# Payload.net
KiCad netlist of a schematic drawn in EAGLE
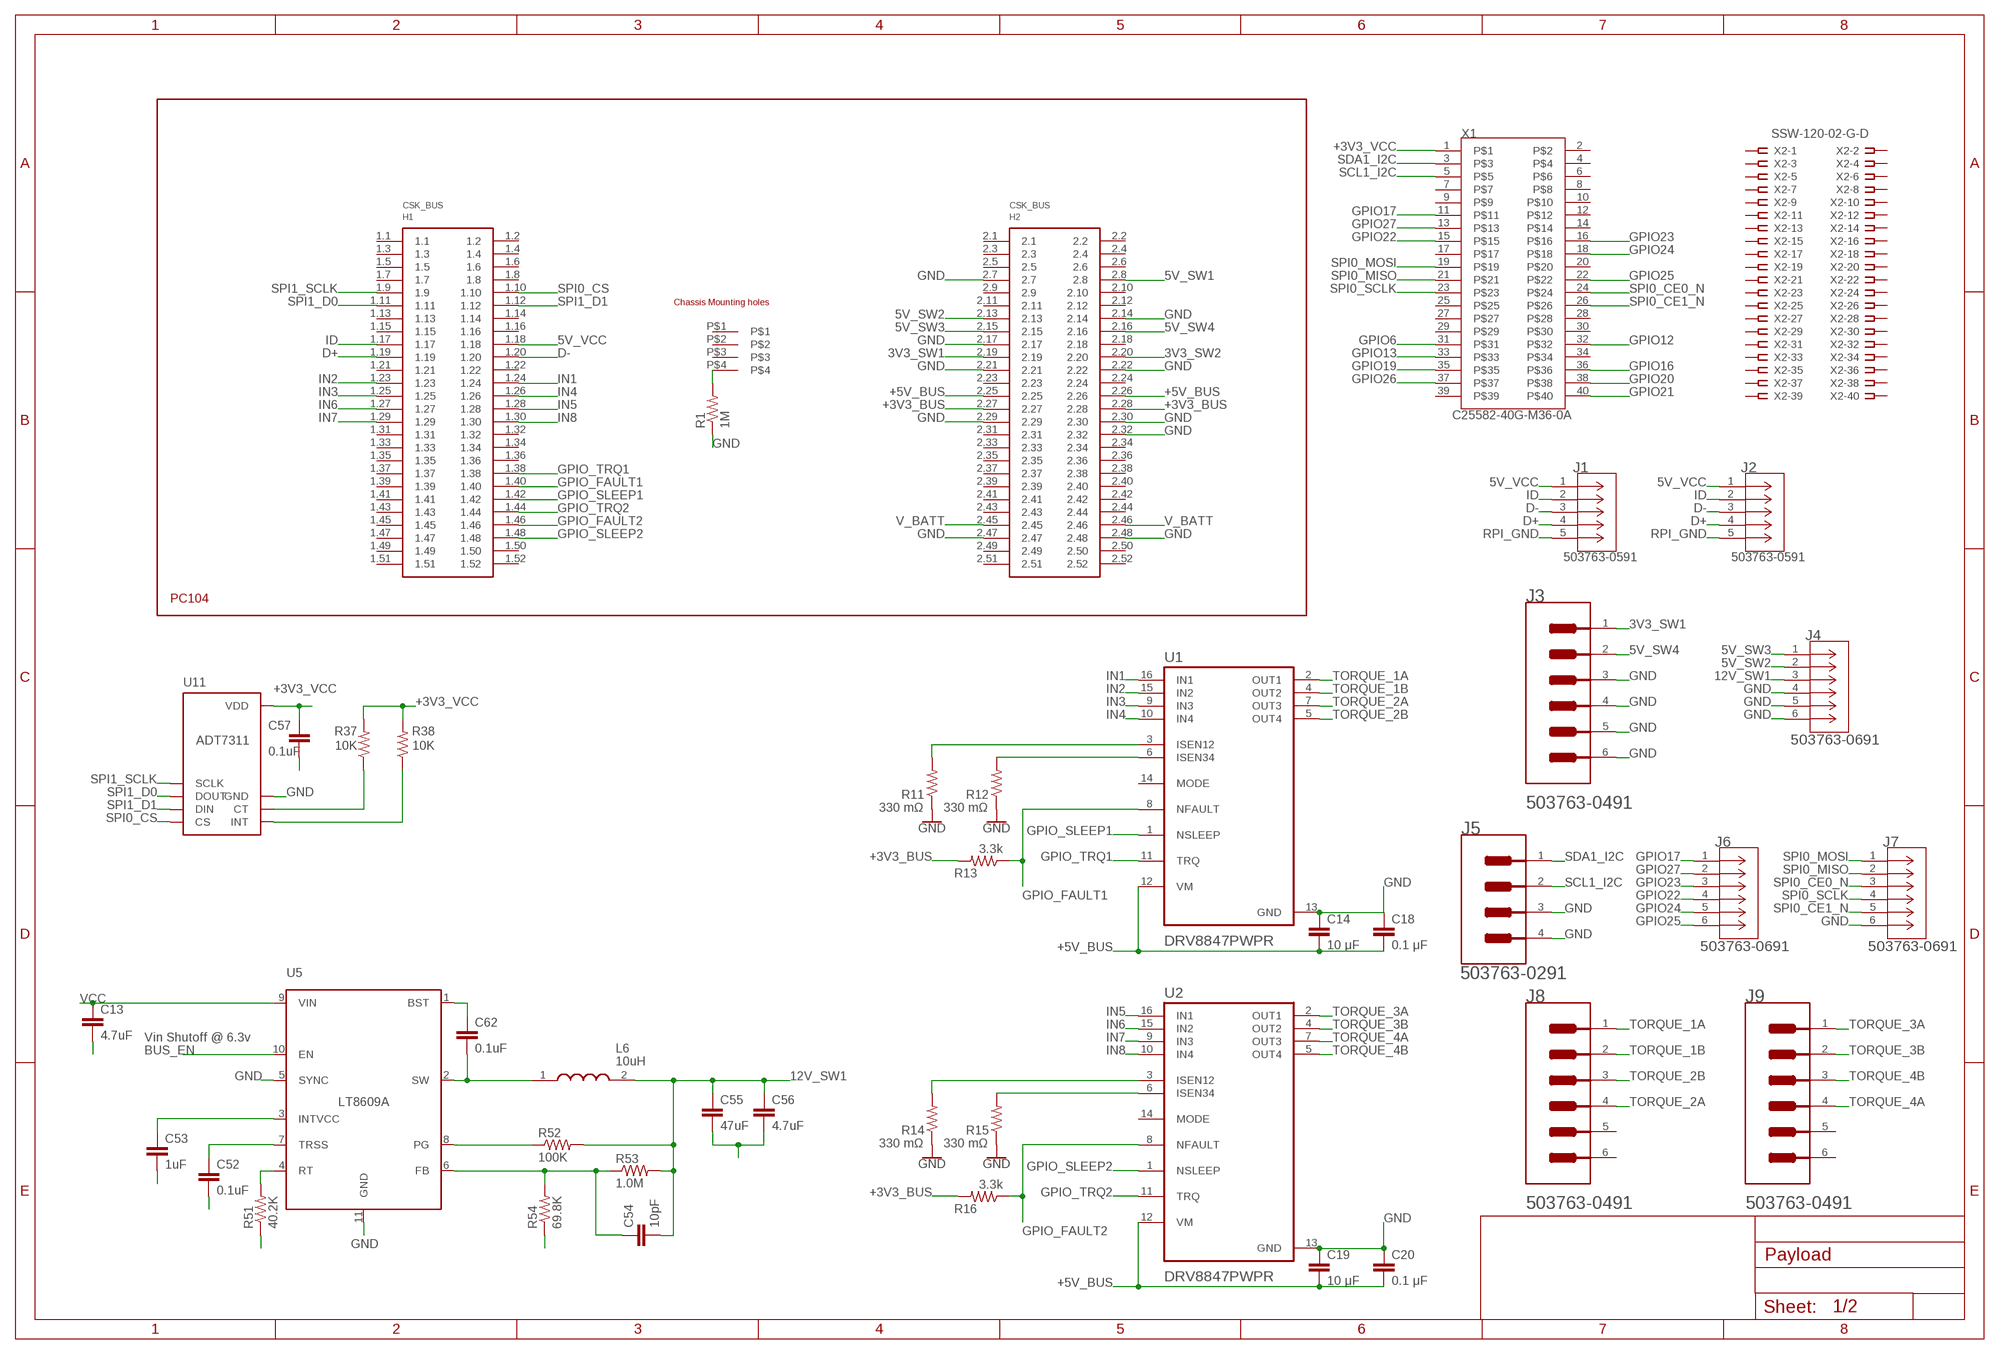
[diagram p0: schematic, sheet 1]
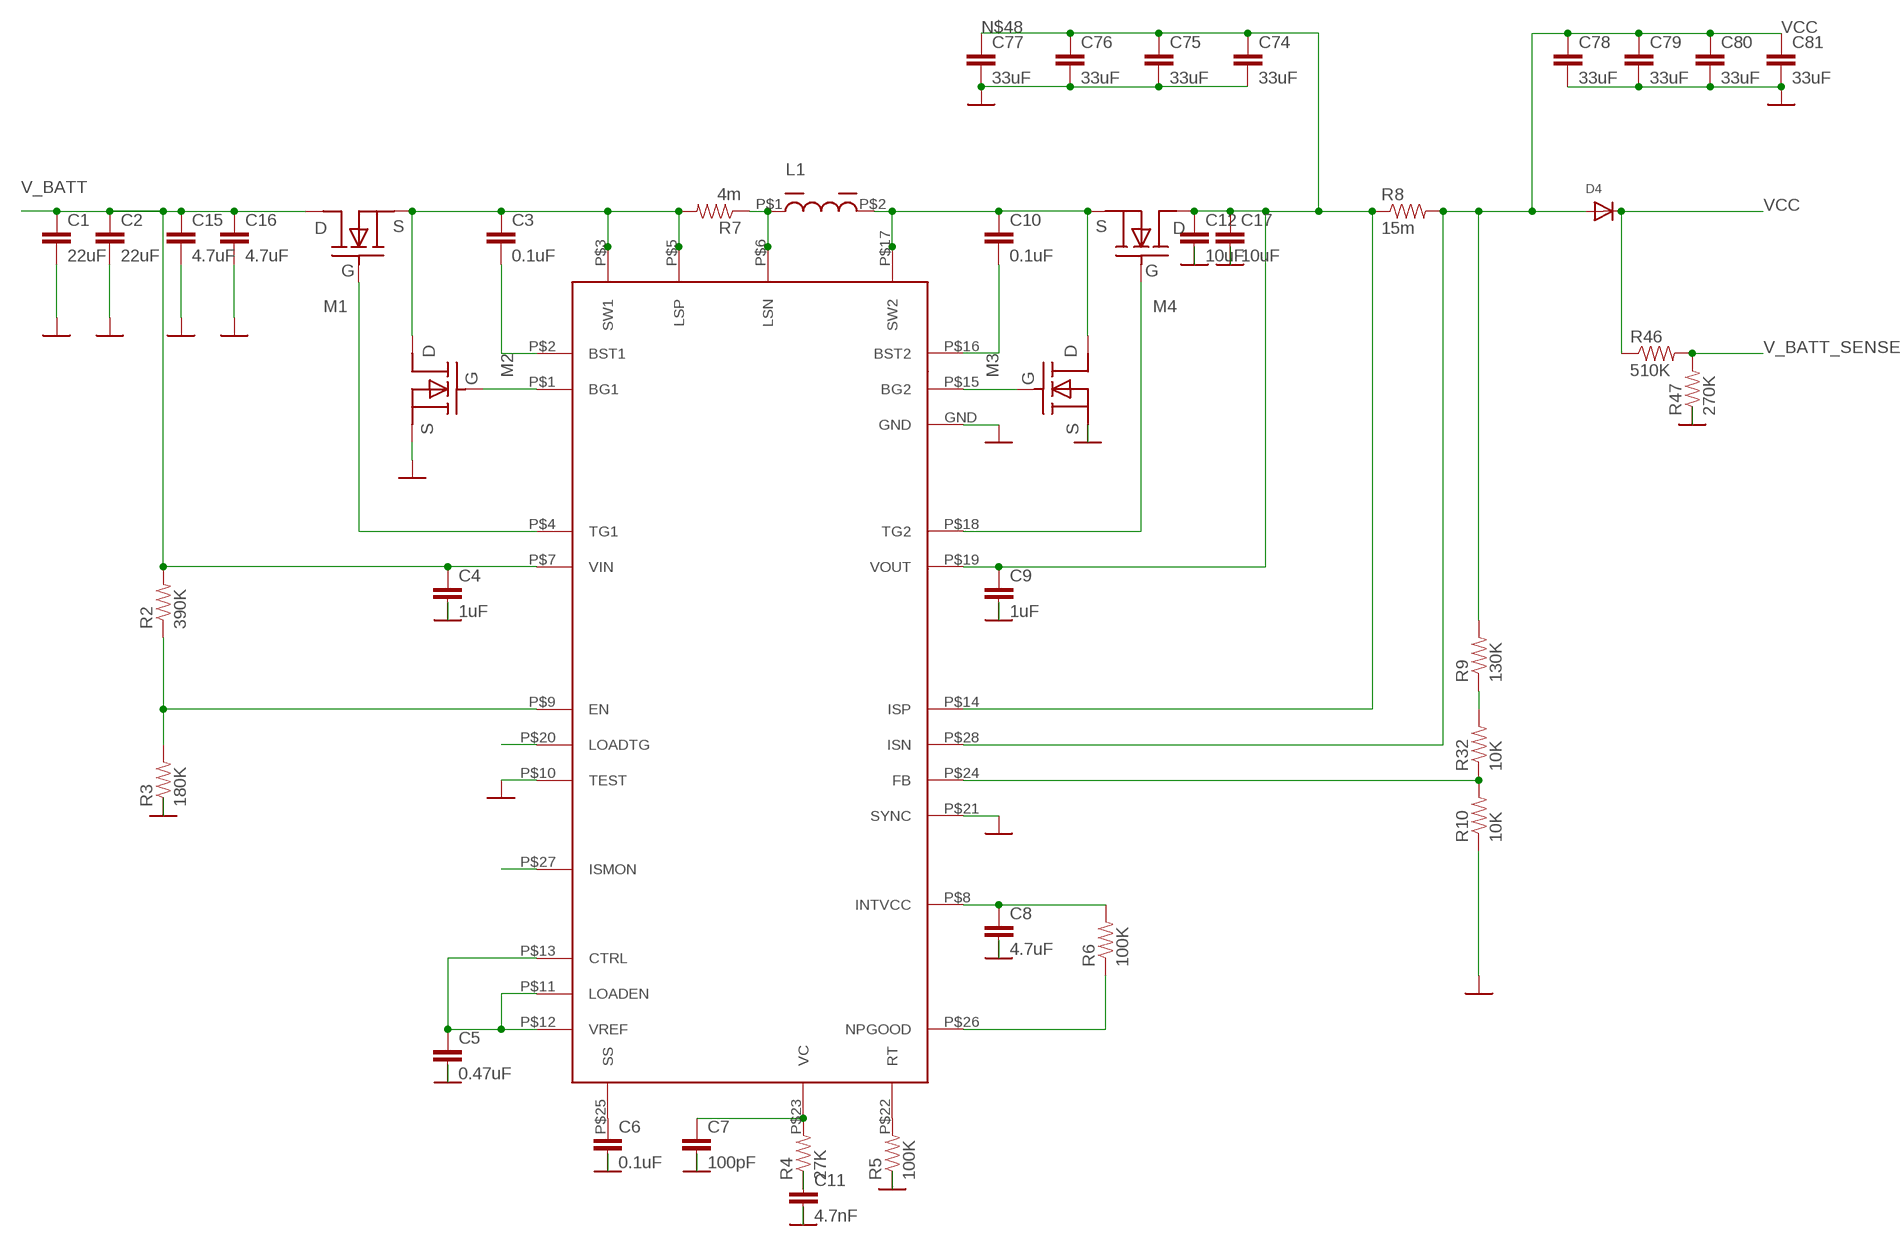
[diagram p1: schematic, sheet 2]

(export (version "E")
  (design (tool "Eeschema 10.0.6"))
  (components
    (comp (ref "C1")
      (value "22uF")
      (footprint "eagle-import:0805")
      (libsource (lib "eagle-import") (part "CAP0805"))
    )
    (comp (ref "C2")
      (value "22uF")
      (footprint "eagle-import:0805")
      (libsource (lib "eagle-import") (part "CAP0805"))
    )
    (comp (ref "C3")
      (value "0.1uF")
      (footprint "eagle-import:0805")
      (libsource (lib "eagle-import") (part "CAP0805"))
    )
    (comp (ref "C4")
      (value "1uF")
      (footprint "eagle-import:0805")
      (libsource (lib "eagle-import") (part "CAP0805"))
    )
    (comp (ref "C5")
      (value "0.47uF")
      (footprint "eagle-import:0805")
      (libsource (lib "eagle-import") (part "CAP0805"))
    )
    (comp (ref "C6")
      (value "0.1uF")
      (footprint "eagle-import:0805")
      (libsource (lib "eagle-import") (part "CAP0805"))
    )
    (comp (ref "C7")
      (value "100pF")
      (footprint "eagle-import:0805")
      (libsource (lib "eagle-import") (part "CAP0805"))
    )
    (comp (ref "C8")
      (value "4.7uF")
      (footprint "eagle-import:0805")
      (libsource (lib "eagle-import") (part "CAP0805"))
    )
    (comp (ref "C9")
      (value "1uF")
      (footprint "eagle-import:0805")
      (libsource (lib "eagle-import") (part "CAP0805"))
    )
    (comp (ref "C10")
      (value "0.1uF")
      (footprint "eagle-import:0805")
      (libsource (lib "eagle-import") (part "CAP0805"))
    )
    (comp (ref "C11")
      (value "4.7nF")
      (footprint "eagle-import:0805")
      (libsource (lib "eagle-import") (part "CAP0805"))
    )
    (comp (ref "C12")
      (value "10uF")
      (footprint "eagle-import:0805")
      (libsource (lib "eagle-import") (part "CAP0805"))
    )
    (comp (ref "C15")
      (value "4.7uF")
      (footprint "eagle-import:0805")
      (libsource (lib "eagle-import") (part "CAP0805"))
    )
    (comp (ref "C16")
      (value "4.7uF")
      (footprint "eagle-import:0805")
      (libsource (lib "eagle-import") (part "CAP0805"))
    )
    (comp (ref "C17")
      (value "10uF")
      (footprint "eagle-import:0805")
      (libsource (lib "eagle-import") (part "CAP0805"))
    )
    (comp (ref "C74")
      (value "33uF")
      (footprint "eagle-import:1206")
      (libsource (lib "eagle-import") (part "CAP1206"))
    )
    (comp (ref "C75")
      (value "33uF")
      (footprint "eagle-import:1206")
      (libsource (lib "eagle-import") (part "CAP1206"))
    )
    (comp (ref "C76")
      (value "33uF")
      (footprint "eagle-import:1206")
      (libsource (lib "eagle-import") (part "CAP1206"))
    )
    (comp (ref "C77")
      (value "33uF")
      (footprint "eagle-import:1206")
      (libsource (lib "eagle-import") (part "CAP1206"))
    )
    (comp (ref "C78")
      (value "33uF")
      (footprint "eagle-import:1206")
      (libsource (lib "eagle-import") (part "CAP1206"))
    )
    (comp (ref "C79")
      (value "33uF")
      (footprint "eagle-import:1206")
      (libsource (lib "eagle-import") (part "CAP1206"))
    )
    (comp (ref "C80")
      (value "33uF")
      (footprint "eagle-import:1206")
      (libsource (lib "eagle-import") (part "CAP1206"))
    )
    (comp (ref "C81")
      (value "33uF")
      (footprint "eagle-import:1206")
      (libsource (lib "eagle-import") (part "CAP1206"))
    )
    (comp (ref "D4")
      (value "DIODE_SOD-123FL")
      (footprint "eagle-import:SOD-123FL")
      (libsource (lib "eagle-import") (part "DIODE_SOD-123FL"))
    )
    (comp (ref "L1")
      (value "6uH")
      (footprint "eagle-import:7443551600")
      (libsource (lib "eagle-import") (part "7443551600"))
    )
    (comp (ref "M1")
      (value "BSZ100N06LS3")
      (footprint "eagle-import:BSZ100N06LS3")
      (libsource (lib "eagle-import") (part "BSZ100N06LS3"))
    )
    (comp (ref "M2")
      (value "BSZ100N06LS3")
      (footprint "eagle-import:BSZ100N06LS3")
      (libsource (lib "eagle-import") (part "BSZ100N06LS3"))
    )
    (comp (ref "M3")
      (value "BSZ033NE2LS5")
      (footprint "eagle-import:BSZ100N06LS3")
      (libsource (lib "eagle-import") (part "BSZ100N06LS3"))
    )
    (comp (ref "M4")
      (value "BSZ033NE2LS5")
      (footprint "eagle-import:BSZ100N06LS3")
      (libsource (lib "eagle-import") (part "BSZ100N06LS3"))
    )
    (comp (ref "R2")
      (value "390K")
      (footprint "eagle-import:0805")
      (libsource (lib "eagle-import") (part "RESISTOR0805-RES"))
    )
    (comp (ref "R3")
      (value "180K")
      (footprint "eagle-import:0805")
      (libsource (lib "eagle-import") (part "RESISTOR0805-RES"))
    )
    (comp (ref "R4")
      (value "27K")
      (footprint "eagle-import:0805")
      (libsource (lib "eagle-import") (part "RESISTOR0805-RES"))
    )
    (comp (ref "R5")
      (value "100K")
      (footprint "eagle-import:0805")
      (libsource (lib "eagle-import") (part "RESISTOR0805-RES"))
    )
    (comp (ref "R6")
      (value "100K")
      (footprint "eagle-import:0805")
      (libsource (lib "eagle-import") (part "RESISTOR0805-RES"))
    )
    (comp (ref "R7")
      (value "4m")
      (footprint "eagle-import:0805")
      (libsource (lib "eagle-import") (part "RESISTOR0805-RES"))
    )
    (comp (ref "R8")
      (value "15m")
      (footprint "eagle-import:0805")
      (libsource (lib "eagle-import") (part "RESISTOR0805-RES"))
    )
    (comp (ref "R9")
      (value "130K")
      (footprint "eagle-import:0805")
      (libsource (lib "eagle-import") (part "RESISTOR0805-RES"))
    )
    (comp (ref "R10")
      (value "10K")
      (footprint "eagle-import:0805")
      (libsource (lib "eagle-import") (part "RESISTOR0805-RES"))
    )
    (comp (ref "R32")
      (value "10K")
      (footprint "eagle-import:0805")
      (libsource (lib "eagle-import") (part "RESISTOR0805-RES"))
    )
    (comp (ref "R46")
      (value "510K")
      (footprint "eagle-import:0805")
      (libsource (lib "eagle-import") (part "RESISTOR0805-RES"))
    )
    (comp (ref "R47")
      (value "270K")
      (footprint "eagle-import:0805")
      (libsource (lib "eagle-import") (part "RESISTOR0805-RES"))
    )
    (comp (ref "U$2")
      (value "LT8309EFE")
      (footprint "eagle-import:LT8309EFE")
      (libsource (lib "eagle-import") (part "LT8309EFE"))
    )
    (comp (ref "C13")
      (value "4.7uF")
      (footprint "eagle-import:0805")
      (libsource (lib "eagle-import") (part "CAP0805"))
    )
    (comp (ref "C14")
      (value "10 μF")
      (footprint "eagle-import:0805")
      (libsource (lib "eagle-import") (part "CAP0805"))
    )
    (comp (ref "C18")
      (value "0.1 μF")
      (footprint "eagle-import:0805")
      (libsource (lib "eagle-import") (part "CAP0805"))
    )
    (comp (ref "C19")
      (value "10 μF")
      (footprint "eagle-import:0805")
      (libsource (lib "eagle-import") (part "CAP0805"))
    )
    (comp (ref "C20")
      (value "0.1 μF")
      (footprint "eagle-import:0805")
      (libsource (lib "eagle-import") (part "CAP0805"))
    )
    (comp (ref "C52")
      (value "0.1uF")
      (footprint "eagle-import:0805")
      (libsource (lib "eagle-import") (part "CAP0805"))
    )
    (comp (ref "C53")
      (value "1uF")
      (footprint "eagle-import:0805")
      (libsource (lib "eagle-import") (part "CAP0805"))
    )
    (comp (ref "C54")
      (value "10pF")
      (footprint "eagle-import:0805")
      (libsource (lib "eagle-import") (part "CAP0805"))
    )
    (comp (ref "C55")
      (value "47uF")
      (footprint "eagle-import:1210")
      (libsource (lib "eagle-import") (part "CAP1210"))
    )
    (comp (ref "C56")
      (value "4.7uF")
      (footprint "eagle-import:0805")
      (libsource (lib "eagle-import") (part "CAP0805"))
    )
    (comp (ref "C57")
      (value "0.1uF")
      (footprint "eagle-import:0805")
      (libsource (lib "eagle-import") (part "CAP0805"))
    )
    (comp (ref "C62")
      (value "0.1uF")
      (footprint "eagle-import:0805")
      (libsource (lib "eagle-import") (part "CAP0805"))
    )
    (comp (ref "H1")
      (value "PC104_WCONN")
      (footprint "eagle-import:PC104_WCONN")
      (libsource (lib "eagle-import") (part "PC104_WCONN"))
    )
    (comp (ref "J1")
      (value "503763-0591")
      (footprint "eagle-import:CONN_5037630591_MOL")
      (fields (field (name "COPYRIGHT") "Copyright (C) 2018 Accelerated Designs. All rights reserved"))
      (libsource (lib "eagle-import") (part "503763-0591"))
    )
    (comp (ref "J2")
      (value "503763-0591")
      (footprint "eagle-import:CONN_5037630591_MOL")
      (fields (field (name "COPYRIGHT") "Copyright (C) 2018 Accelerated Designs. All rights reserved"))
      (libsource (lib "eagle-import") (part "503763-0591"))
    )
    (comp (ref "J3")
      (value "MOLEX_503763-0491MOLEX_503763-0491_0_0")
      (footprint "eagle-import:MOLEX_503763-0491_0")
      (fields
        (field (name "DIGIKEY_PART_NUMBER") "WM10655CT-ND")
        (field (name "MF") "Molex")
        (field (name "MOUSER_PART_NUMBER") "538-503763-0491")
      )
      (libsource (lib "eagle-import") (part "MOLEX_503763-0491MOLEX_503763-0491_0_0"))
    )
    (comp (ref "J4")
      (value "503763-0691")
      (footprint "eagle-import:CONN_503763-0691_MOL")
      (fields (field (name "COPYRIGHT") "Copyright (C) 2018 Accelerated Designs. All rights reserved"))
      (libsource (lib "eagle-import") (part "503763-0691"))
    )
    (comp (ref "J5")
      (value "MOLEX_503763-0291MOLEX_503763-0291_0_0")
      (footprint "eagle-import:MOLEX_503763-0291_0")
      (fields
        (field (name "DIGIKEY_PART_NUMBER") "WM10654CT-ND")
        (field (name "MF") "Molex")
        (field (name "MOUSER_PART_NUMBER") "538-503763-0291")
      )
      (libsource (lib "eagle-import") (part "MOLEX_503763-0291MOLEX_503763-0291_0_0"))
    )
    (comp (ref "J6")
      (value "503763-0691")
      (footprint "eagle-import:CONN_503763-0691_MOL")
      (fields (field (name "COPYRIGHT") "Copyright (C) 2018 Accelerated Designs. All rights reserved"))
      (libsource (lib "eagle-import") (part "503763-0691"))
    )
    (comp (ref "J7")
      (value "503763-0691")
      (footprint "eagle-import:CONN_503763-0691_MOL")
      (fields (field (name "COPYRIGHT") "Copyright (C) 2018 Accelerated Designs. All rights reserved"))
      (libsource (lib "eagle-import") (part "503763-0691"))
    )
    (comp (ref "J8")
      (value "MOLEX_503763-0491MOLEX_503763-0491_0_0")
      (footprint "eagle-import:MOLEX_503763-0491_0")
      (fields
        (field (name "DIGIKEY_PART_NUMBER") "WM10655CT-ND")
        (field (name "MF") "Molex")
        (field (name "MOUSER_PART_NUMBER") "538-503763-0491")
      )
      (libsource (lib "eagle-import") (part "MOLEX_503763-0491MOLEX_503763-0491_0_0"))
    )
    (comp (ref "J9")
      (value "MOLEX_503763-0491MOLEX_503763-0491_0_0")
      (footprint "eagle-import:MOLEX_503763-0491_0")
      (fields
        (field (name "DIGIKEY_PART_NUMBER") "WM10655CT-ND")
        (field (name "MF") "Molex")
        (field (name "MOUSER_PART_NUMBER") "538-503763-0491")
      )
      (libsource (lib "eagle-import") (part "MOLEX_503763-0491MOLEX_503763-0491_0_0"))
    )
    (comp (ref "L6")
      (value "10uH")
      (footprint "eagle-import:XFL4030472MEB")
      (fields
        (field (name "ARROW_PART_NUMBER") "XFL4020-222MEC")
        (field (name "MOUSER_PART_NUMBER") "994-XFL4020-222MEC")
      )
      (libsource (lib "eagle-import") (part "XFL4020-222MEC"))
    )
    (comp (ref "R1")
      (value "1M")
      (footprint "eagle-import:0805")
      (libsource (lib "eagle-import") (part "RESISTOR0805-RES"))
    )
    (comp (ref "R11")
      (value "330 mΩ")
      (footprint "eagle-import:0805")
      (libsource (lib "eagle-import") (part "RESISTOR0805-RES"))
    )
    (comp (ref "R12")
      (value "330 mΩ")
      (footprint "eagle-import:0805")
      (libsource (lib "eagle-import") (part "RESISTOR0805-RES"))
    )
    (comp (ref "R13")
      (value "3.3k")
      (footprint "eagle-import:0805")
      (libsource (lib "eagle-import") (part "RESISTOR0805-RES"))
    )
    (comp (ref "R14")
      (value "330 mΩ")
      (footprint "eagle-import:0805")
      (libsource (lib "eagle-import") (part "RESISTOR0805-RES"))
    )
    (comp (ref "R15")
      (value "330 mΩ")
      (footprint "eagle-import:0805")
      (libsource (lib "eagle-import") (part "RESISTOR0805-RES"))
    )
    (comp (ref "R16")
      (value "3.3k")
      (footprint "eagle-import:0805")
      (libsource (lib "eagle-import") (part "RESISTOR0805-RES"))
    )
    (comp (ref "R37")
      (value "10K")
      (footprint "eagle-import:0805")
      (libsource (lib "eagle-import") (part "RESISTOR0805-RES"))
    )
    (comp (ref "R38")
      (value "10K")
      (footprint "eagle-import:0805")
      (libsource (lib "eagle-import") (part "RESISTOR0805-RES"))
    )
    (comp (ref "R51")
      (value "40.2K")
      (footprint "eagle-import:0805")
      (libsource (lib "eagle-import") (part "RESISTOR0805-RES"))
    )
    (comp (ref "R52")
      (value "100K")
      (footprint "eagle-import:0805")
      (libsource (lib "eagle-import") (part "RESISTOR0805-RES"))
    )
    (comp (ref "R53")
      (value "1.0M")
      (footprint "eagle-import:0805")
      (libsource (lib "eagle-import") (part "RESISTOR0805-RES"))
    )
    (comp (ref "R54")
      (value "69.8K")
      (footprint "eagle-import:0805")
      (libsource (lib "eagle-import") (part "RESISTOR0805-RES"))
    )
    (comp (ref "U1")
      (value "DRV8847PWPR")
      (footprint "eagle-import:SOP65P640X120-17N")
      (fields (field (name "MF") "Texas Instruments"))
      (libsource (lib "eagle-import") (part "DRV8847PWPR"))
    )
    (comp (ref "U2")
      (value "DRV8847PWPR")
      (footprint "eagle-import:SOP65P640X120-17N")
      (fields (field (name "MF") "Texas Instruments"))
      (libsource (lib "eagle-import") (part "DRV8847PWPR"))
    )
    (comp (ref "U5")
      (value "LT8609A")
      (footprint "eagle-import:MSOP-10_MSE")
      (libsource (lib "eagle-import") (part "LT8609A"))
    )
    (comp (ref "U11")
      (value "ADT7311")
      (footprint "eagle-import:SOIC-8")
      (libsource (lib "eagle-import") (part "ADT7311"))
    )
    (comp (ref "X1")
      (value "C25582-40G-M36-0A")
      (footprint "eagle-import:ADAFRUIT_C25582-40G-M36-0A_0")
      (libsource (lib "eagle-import") (part "C25582-40G-M36-0A"))
    )
    (comp (ref "X2")
      (value "SSW-120-02-G-D")
      (footprint "eagle-import:SSW-120-02-G-D")
      (fields (field (name "MF") "Samtec Inc."))
      (libsource (lib "eagle-import") (part "SSW-120-02-G-D"))
    )
  )
  (nets
    (net (code "1") (name "+3V3_BUS") (class "Default")
      (node (ref "H1") (pin "2.27") (pinfunction "2.27_2.27") (pintype "bidirectional"))
      (node (ref "H1") (pin "2.28") (pinfunction "2.28_2.28") (pintype "bidirectional"))
      (node (ref "R13") (pin "2") (pinfunction "2_2") (pintype "passive"))
      (node (ref "R16") (pin "2") (pinfunction "2_2") (pintype "passive"))
    )
    (net (code "2") (name "+3V3_VCC") (class "Default")
      (node (ref "C57") (pin "1") (pinfunction "1_1") (pintype "passive"))
      (node (ref "R37") (pin "2") (pinfunction "2_2") (pintype "passive"))
      (node (ref "R38") (pin "2") (pinfunction "2_2") (pintype "passive"))
      (node (ref "U11") (pin "8") (pinfunction "VDD_8") (pintype "bidirectional"))
      (node (ref "X1") (pin "1") (pinfunction "P$1_1") (pintype "bidirectional"))
    )
    (net (code "3") (name "+5V_BUS") (class "Default")
      (node (ref "C14") (pin "2") (pinfunction "2_2") (pintype "passive"))
      (node (ref "C18") (pin "2") (pinfunction "2_2") (pintype "passive"))
      (node (ref "C19") (pin "2") (pinfunction "2_2") (pintype "passive"))
      (node (ref "C20") (pin "2") (pinfunction "2_2") (pintype "passive"))
      (node (ref "H1") (pin "2.25") (pinfunction "2.25_2.25") (pintype "bidirectional"))
      (node (ref "H1") (pin "2.26") (pinfunction "2.26_2.26") (pintype "bidirectional"))
      (node (ref "U1") (pin "12") (pinfunction "VM_12") (pintype "bidirectional"))
      (node (ref "U2") (pin "12") (pinfunction "VM_12") (pintype "bidirectional"))
    )
    (net (code "4") (name "3V3_SW1") (class "Default")
      (node (ref "H1") (pin "2.19") (pinfunction "2.19_2.19") (pintype "bidirectional"))
      (node (ref "J3") (pin "1") (pinfunction "1_1") (pintype "passive"))
    )
    (net (code "5") (name "3V3_SW2") (class "Default")
      (node (ref "H1") (pin "2.20") (pinfunction "2.20_2.20") (pintype "bidirectional"))
    )
    (net (code "6") (name "5V_SW1") (class "Default")
      (node (ref "H1") (pin "2.8") (pinfunction "2.8_2.8") (pintype "bidirectional"))
    )
    (net (code "7") (name "5V_SW2") (class "Default")
      (node (ref "H1") (pin "2.13") (pinfunction "2.13_2.13") (pintype "bidirectional"))
      (node (ref "J4") (pin "2") (pinfunction "2_2") (pintype "passive"))
    )
    (net (code "8") (name "5V_SW3") (class "Default")
      (node (ref "H1") (pin "2.15") (pinfunction "2.15_2.15") (pintype "bidirectional"))
      (node (ref "J4") (pin "1") (pinfunction "1_1") (pintype "passive"))
    )
    (net (code "9") (name "5V_SW4") (class "Default")
      (node (ref "H1") (pin "2.16") (pinfunction "2.16_2.16") (pintype "bidirectional"))
      (node (ref "J3") (pin "2") (pinfunction "2_2") (pintype "passive"))
    )
    (net (code "10") (name "5V_VCC") (class "Default")
      (node (ref "H1") (pin "1.18") (pinfunction "1.18_1.18") (pintype "bidirectional"))
      (node (ref "J1") (pin "1") (pinfunction "1_1") (pintype "passive"))
      (node (ref "J2") (pin "1") (pinfunction "1_1") (pintype "passive"))
    )
    (net (code "11") (name "12V_SW1") (class "Default")
      (node (ref "C54") (pin "2") (pinfunction "2_2") (pintype "passive"))
      (node (ref "C55") (pin "1") (pinfunction "1_1") (pintype "passive"))
      (node (ref "C56") (pin "1") (pinfunction "1_1") (pintype "passive"))
      (node (ref "J4") (pin "3") (pinfunction "3_3") (pintype "passive"))
      (node (ref "L6") (pin "2") (pinfunction "2_2") (pintype "bidirectional"))
      (node (ref "R52") (pin "2") (pinfunction "2_2") (pintype "passive"))
      (node (ref "R53") (pin "2") (pinfunction "2_2") (pintype "passive"))
    )
    (net (code "12") (name "BUS_EN") (class "Default")
      (node (ref "U5") (pin "10") (pinfunction "EN_10") (pintype "bidirectional"))
    )
    (net (code "13") (name "D+") (class "Default")
      (node (ref "H1") (pin "1.19") (pinfunction "1.19_1.19") (pintype "bidirectional"))
      (node (ref "J1") (pin "4") (pinfunction "4_4") (pintype "passive"))
      (node (ref "J2") (pin "4") (pinfunction "4_4") (pintype "passive"))
    )
    (net (code "14") (name "D-") (class "Default")
      (node (ref "H1") (pin "1.20") (pinfunction "1.20_1.20") (pintype "bidirectional"))
      (node (ref "J1") (pin "3") (pinfunction "3_3") (pintype "passive"))
      (node (ref "J2") (pin "3") (pinfunction "3_3") (pintype "passive"))
    )
    (net (code "15") (name "GND") (class "Default")
      (node (ref "C1") (pin "2") (pinfunction "2_2") (pintype "passive"))
      (node (ref "C11") (pin "2") (pinfunction "2_2") (pintype "passive"))
      (node (ref "C12") (pin "2") (pinfunction "2_2") (pintype "passive"))
      (node (ref "C14") (pin "1") (pinfunction "1_1") (pintype "passive"))
      (node (ref "C15") (pin "2") (pinfunction "2_2") (pintype "passive"))
      (node (ref "C16") (pin "2") (pinfunction "2_2") (pintype "passive"))
      (node (ref "C17") (pin "2") (pinfunction "2_2") (pintype "passive"))
      (node (ref "C18") (pin "1") (pinfunction "1_1") (pintype "passive"))
      (node (ref "C19") (pin "1") (pinfunction "1_1") (pintype "passive"))
      (node (ref "C2") (pin "2") (pinfunction "2_2") (pintype "passive"))
      (node (ref "C20") (pin "1") (pinfunction "1_1") (pintype "passive"))
      (node (ref "C4") (pin "2") (pinfunction "2_2") (pintype "passive"))
      (node (ref "C5") (pin "2") (pinfunction "2_2") (pintype "passive"))
      (node (ref "C52") (pin "2") (pinfunction "2_2") (pintype "passive"))
      (node (ref "C53") (pin "2") (pinfunction "2_2") (pintype "passive"))
      (node (ref "C55") (pin "2") (pinfunction "2_2") (pintype "passive"))
      (node (ref "C56") (pin "2") (pinfunction "2_2") (pintype "passive"))
      (node (ref "C57") (pin "2") (pinfunction "2_2") (pintype "passive"))
      (node (ref "C6") (pin "2") (pinfunction "2_2") (pintype "passive"))
      (node (ref "C7") (pin "2") (pinfunction "2_2") (pintype "passive"))
      (node (ref "C74") (pin "2") (pinfunction "2_2") (pintype "passive"))
      (node (ref "C75") (pin "2") (pinfunction "2_2") (pintype "passive"))
      (node (ref "C76") (pin "2") (pinfunction "2_2") (pintype "passive"))
      (node (ref "C77") (pin "2") (pinfunction "2_2") (pintype "passive"))
      (node (ref "C78") (pin "2") (pinfunction "2_2") (pintype "passive"))
      (node (ref "C79") (pin "2") (pinfunction "2_2") (pintype "passive"))
      (node (ref "C8") (pin "2") (pinfunction "2_2") (pintype "passive"))
      (node (ref "C80") (pin "2") (pinfunction "2_2") (pintype "passive"))
      (node (ref "C81") (pin "2") (pinfunction "2_2") (pintype "passive"))
      (node (ref "C9") (pin "2") (pinfunction "2_2") (pintype "passive"))
      (node (ref "H1") (pin "2.14") (pinfunction "2.14_2.14") (pintype "bidirectional"))
      (node (ref "H1") (pin "2.17") (pinfunction "2.17_2.17") (pintype "bidirectional"))
      (node (ref "H1") (pin "2.21") (pinfunction "2.21_2.21") (pintype "bidirectional"))
      (node (ref "H1") (pin "2.22") (pinfunction "2.22_2.22") (pintype "bidirectional"))
      (node (ref "H1") (pin "2.29") (pinfunction "2.29_2.29") (pintype "bidirectional"))
      (node (ref "H1") (pin "2.30") (pinfunction "2.30_2.30") (pintype "bidirectional"))
      (node (ref "H1") (pin "2.32") (pinfunction "2.32_2.32") (pintype "bidirectional"))
      (node (ref "H1") (pin "2.47") (pinfunction "2.47_2.47") (pintype "bidirectional"))
      (node (ref "H1") (pin "2.48") (pinfunction "2.48_2.48") (pintype "bidirectional"))
      (node (ref "H1") (pin "2.7") (pinfunction "2.7_2.7") (pintype "bidirectional"))
      (node (ref "J3") (pin "3") (pinfunction "3_3") (pintype "passive"))
      (node (ref "J3") (pin "4") (pinfunction "4_4") (pintype "passive"))
      (node (ref "J3") (pin "5") (pinfunction "MNT_1_5") (pintype "passive"))
      (node (ref "J3") (pin "6") (pinfunction "MNT_2_6") (pintype "passive"))
      (node (ref "J4") (pin "4") (pinfunction "4_4") (pintype "passive"))
      (node (ref "J4") (pin "5") (pinfunction "5_5") (pintype "passive"))
      (node (ref "J4") (pin "6") (pinfunction "6_6") (pintype "passive"))
      (node (ref "J5") (pin "3") (pinfunction "MNT_1_3") (pintype "bidirectional"))
      (node (ref "J5") (pin "4") (pinfunction "MNT_2_4") (pintype "bidirectional"))
      (node (ref "J7") (pin "6") (pinfunction "6_6") (pintype "passive"))
      (node (ref "M2") (pin "P$2") (pinfunction "S_P$2") (pintype "input"))
      (node (ref "M2") (pin "P$3") (pinfunction "S_P$3") (pintype "input"))
      (node (ref "M2") (pin "P$4") (pinfunction "S_P$4") (pintype "input"))
      (node (ref "M3") (pin "P$2") (pinfunction "S_P$2") (pintype "input"))
      (node (ref "M3") (pin "P$3") (pinfunction "S_P$3") (pintype "input"))
      (node (ref "M3") (pin "P$4") (pinfunction "S_P$4") (pintype "input"))
      (node (ref "R1") (pin "1") (pinfunction "1_1") (pintype "passive"))
      (node (ref "R10") (pin "1") (pinfunction "1_1") (pintype "passive"))
      (node (ref "R11") (pin "1") (pinfunction "1_1") (pintype "passive"))
      (node (ref "R12") (pin "1") (pinfunction "1_1") (pintype "passive"))
      (node (ref "R14") (pin "1") (pinfunction "1_1") (pintype "passive"))
      (node (ref "R15") (pin "1") (pinfunction "1_1") (pintype "passive"))
      (node (ref "R3") (pin "1") (pinfunction "1_1") (pintype "passive"))
      (node (ref "R47") (pin "1") (pinfunction "1_1") (pintype "passive"))
      (node (ref "R5") (pin "1") (pinfunction "1_1") (pintype "passive"))
      (node (ref "R51") (pin "1") (pinfunction "1_1") (pintype "passive"))
      (node (ref "R54") (pin "1") (pinfunction "1_1") (pintype "passive"))
      (node (ref "U$2") (pin "GND") (pinfunction "GND_GND") (pintype "bidirectional"))
      (node (ref "U$2") (pin "P$10") (pinfunction "TEST_P$10") (pintype "bidirectional"))
      (node (ref "U$2") (pin "P$21") (pinfunction "SYNC_P$21") (pintype "bidirectional"))
      (node (ref "U1") (pin "13") (pinfunction "GND_13") (pintype "power_in"))
      (node (ref "U11") (pin "7") (pinfunction "GND_7") (pintype "bidirectional"))
      (node (ref "U2") (pin "13") (pinfunction "GND_13") (pintype "power_in"))
      (node (ref "U5") (pin "11") (pinfunction "GND_11") (pintype "bidirectional"))
      (node (ref "U5") (pin "5") (pinfunction "SYNC_5") (pintype "bidirectional"))
    )
    (net (code "16") (name "GPIO6") (class "Default")
      (node (ref "X1") (pin "31") (pinfunction "P$31_31") (pintype "bidirectional"))
    )
    (net (code "17") (name "GPIO12") (class "Default")
      (node (ref "X1") (pin "32") (pinfunction "P$32_32") (pintype "bidirectional"))
    )
    (net (code "18") (name "GPIO13") (class "Default")
      (node (ref "X1") (pin "33") (pinfunction "P$33_33") (pintype "bidirectional"))
    )
    (net (code "19") (name "GPIO16") (class "Default")
      (node (ref "X1") (pin "36") (pinfunction "P$36_36") (pintype "bidirectional"))
    )
    (net (code "20") (name "GPIO17") (class "Default")
      (node (ref "J6") (pin "1") (pinfunction "1_1") (pintype "passive"))
      (node (ref "X1") (pin "11") (pinfunction "P$11_11") (pintype "bidirectional"))
    )
    (net (code "21") (name "GPIO19") (class "Default")
      (node (ref "X1") (pin "35") (pinfunction "P$35_35") (pintype "bidirectional"))
    )
    (net (code "22") (name "GPIO20") (class "Default")
      (node (ref "X1") (pin "38") (pinfunction "P$38_38") (pintype "bidirectional"))
    )
    (net (code "23") (name "GPIO21") (class "Default")
      (node (ref "X1") (pin "40") (pinfunction "P$40_40") (pintype "bidirectional"))
    )
    (net (code "24") (name "GPIO22") (class "Default")
      (node (ref "J6") (pin "4") (pinfunction "4_4") (pintype "passive"))
      (node (ref "X1") (pin "15") (pinfunction "P$15_15") (pintype "bidirectional"))
    )
    (net (code "25") (name "GPIO23") (class "Default")
      (node (ref "J6") (pin "3") (pinfunction "3_3") (pintype "passive"))
      (node (ref "X1") (pin "16") (pinfunction "P$16_16") (pintype "bidirectional"))
    )
    (net (code "26") (name "GPIO24") (class "Default")
      (node (ref "J6") (pin "5") (pinfunction "5_5") (pintype "passive"))
      (node (ref "X1") (pin "18") (pinfunction "P$18_18") (pintype "bidirectional"))
    )
    (net (code "27") (name "GPIO25") (class "Default")
      (node (ref "J6") (pin "6") (pinfunction "6_6") (pintype "passive"))
      (node (ref "X1") (pin "22") (pinfunction "P$22_22") (pintype "bidirectional"))
    )
    (net (code "28") (name "GPIO26") (class "Default")
      (node (ref "X1") (pin "37") (pinfunction "P$37_37") (pintype "bidirectional"))
    )
    (net (code "29") (name "GPIO27") (class "Default")
      (node (ref "J6") (pin "2") (pinfunction "2_2") (pintype "passive"))
      (node (ref "X1") (pin "13") (pinfunction "P$13_13") (pintype "bidirectional"))
    )
    (net (code "30") (name "GPIO_FAULT1") (class "Default")
      (node (ref "H1") (pin "1.40") (pinfunction "1.40_1.40") (pintype "bidirectional"))
      (node (ref "R13") (pin "1") (pinfunction "1_1") (pintype "passive"))
      (node (ref "U1") (pin "8") (pinfunction "NFAULT_8") (pintype "bidirectional"))
    )
    (net (code "31") (name "GPIO_FAULT2") (class "Default")
      (node (ref "H1") (pin "1.46") (pinfunction "1.46_1.46") (pintype "bidirectional"))
      (node (ref "R16") (pin "1") (pinfunction "1_1") (pintype "passive"))
      (node (ref "U2") (pin "8") (pinfunction "NFAULT_8") (pintype "bidirectional"))
    )
    (net (code "32") (name "GPIO_SLEEP1") (class "Default")
      (node (ref "H1") (pin "1.42") (pinfunction "1.42_1.42") (pintype "bidirectional"))
      (node (ref "U1") (pin "1") (pinfunction "NSLEEP_1") (pintype "bidirectional"))
    )
    (net (code "33") (name "GPIO_SLEEP2") (class "Default")
      (node (ref "H1") (pin "1.48") (pinfunction "1.48_1.48") (pintype "bidirectional"))
      (node (ref "U2") (pin "1") (pinfunction "NSLEEP_1") (pintype "bidirectional"))
    )
    (net (code "34") (name "GPIO_TRQ1") (class "Default")
      (node (ref "H1") (pin "1.38") (pinfunction "1.38_1.38") (pintype "bidirectional"))
      (node (ref "U1") (pin "11") (pinfunction "TRQ_11") (pintype "bidirectional"))
    )
    (net (code "35") (name "GPIO_TRQ2") (class "Default")
      (node (ref "H1") (pin "1.44") (pinfunction "1.44_1.44") (pintype "bidirectional"))
      (node (ref "U2") (pin "11") (pinfunction "TRQ_11") (pintype "bidirectional"))
    )
    (net (code "36") (name "ID") (class "Default")
      (node (ref "H1") (pin "1.17") (pinfunction "1.17_1.17") (pintype "bidirectional"))
      (node (ref "J1") (pin "2") (pinfunction "2_2") (pintype "passive"))
      (node (ref "J2") (pin "2") (pinfunction "2_2") (pintype "passive"))
    )
    (net (code "37") (name "IN1") (class "Default")
      (node (ref "H1") (pin "1.24") (pinfunction "1.24_1.24") (pintype "bidirectional"))
      (node (ref "U1") (pin "16") (pinfunction "IN1_16") (pintype "input"))
    )
    (net (code "38") (name "IN2") (class "Default")
      (node (ref "H1") (pin "1.23") (pinfunction "1.23_1.23") (pintype "bidirectional"))
      (node (ref "U1") (pin "15") (pinfunction "IN2_15") (pintype "input"))
    )
    (net (code "39") (name "IN3") (class "Default")
      (node (ref "H1") (pin "1.25") (pinfunction "1.25_1.25") (pintype "bidirectional"))
      (node (ref "U1") (pin "9") (pinfunction "IN3_9") (pintype "input"))
    )
    (net (code "40") (name "IN4") (class "Default")
      (node (ref "H1") (pin "1.26") (pinfunction "1.26_1.26") (pintype "bidirectional"))
      (node (ref "U1") (pin "10") (pinfunction "IN4_10") (pintype "input"))
    )
    (net (code "41") (name "IN5") (class "Default")
      (node (ref "H1") (pin "1.28") (pinfunction "1.28_1.28") (pintype "bidirectional"))
      (node (ref "U2") (pin "16") (pinfunction "IN1_16") (pintype "input"))
    )
    (net (code "42") (name "IN6") (class "Default")
      (node (ref "H1") (pin "1.27") (pinfunction "1.27_1.27") (pintype "bidirectional"))
      (node (ref "U2") (pin "15") (pinfunction "IN2_15") (pintype "input"))
    )
    (net (code "43") (name "IN7") (class "Default")
      (node (ref "H1") (pin "1.29") (pinfunction "1.29_1.29") (pintype "bidirectional"))
      (node (ref "U2") (pin "9") (pinfunction "IN3_9") (pintype "input"))
    )
    (net (code "44") (name "IN8") (class "Default")
      (node (ref "H1") (pin "1.30") (pinfunction "1.30_1.30") (pintype "bidirectional"))
      (node (ref "U2") (pin "10") (pinfunction "IN4_10") (pintype "input"))
    )
    (net (code "45") (name "N$48") (class "Default")
      (node (ref "C12") (pin "1") (pinfunction "1_1") (pintype "passive"))
      (node (ref "C17") (pin "1") (pinfunction "1_1") (pintype "passive"))
      (node (ref "C74") (pin "1") (pinfunction "1_1") (pintype "passive"))
      (node (ref "C75") (pin "1") (pinfunction "1_1") (pintype "passive"))
      (node (ref "C76") (pin "1") (pinfunction "1_1") (pintype "passive"))
      (node (ref "C77") (pin "1") (pinfunction "1_1") (pintype "passive"))
      (node (ref "C9") (pin "1") (pinfunction "1_1") (pintype "passive"))
      (node (ref "M4") (pin "P$5") (pinfunction "D_P$5") (pintype "output"))
      (node (ref "M4") (pin "P$6") (pinfunction "D_P$6") (pintype "output"))
      (node (ref "M4") (pin "P$7") (pinfunction "D_P$7") (pintype "output"))
      (node (ref "M4") (pin "P$8") (pinfunction "D_P$8") (pintype "output"))
      (node (ref "M4") (pin "P$9") (pinfunction "D_P$9") (pintype "output"))
      (node (ref "R8") (pin "1") (pinfunction "1_1") (pintype "passive"))
      (node (ref "U$2") (pin "P$14") (pinfunction "ISP_P$14") (pintype "bidirectional"))
      (node (ref "U$2") (pin "P$19") (pinfunction "VOUT_P$19") (pintype "bidirectional"))
    )
    (net (code "46") (name "Net-(C11-Pad1)") (class "Default")
      (node (ref "C11") (pin "1") (pinfunction "1_1") (pintype "passive"))
      (node (ref "R4") (pin "1") (pinfunction "1_1") (pintype "passive"))
    )
    (net (code "47") (name "Net-(H1-PadP$4)") (class "Default")
      (node (ref "H1") (pin "P$4") (pinfunction "P$4_P$4") (pintype "bidirectional"))
      (node (ref "R1") (pin "2") (pinfunction "2_2") (pintype "passive"))
    )
    (net (code "48") (name "Net-(M1-G)") (class "Default")
      (node (ref "M1") (pin "P$1") (pinfunction "G_P$1") (pintype "input"))
      (node (ref "U$2") (pin "P$4") (pinfunction "TG1_P$4") (pintype "bidirectional"))
    )
    (net (code "49") (name "Net-(M2-G)") (class "Default")
      (node (ref "M2") (pin "P$1") (pinfunction "G_P$1") (pintype "input"))
      (node (ref "U$2") (pin "P$1") (pinfunction "BG1_P$1") (pintype "bidirectional"))
    )
    (net (code "50") (name "Net-(M3-G)") (class "Default")
      (node (ref "M3") (pin "P$1") (pinfunction "G_P$1") (pintype "input"))
      (node (ref "U$2") (pin "P$15") (pinfunction "BG2_P$15") (pintype "bidirectional"))
    )
    (net (code "51") (name "Net-(M4-G)") (class "Default")
      (node (ref "M4") (pin "P$1") (pinfunction "G_P$1") (pintype "input"))
      (node (ref "U$2") (pin "P$18") (pinfunction "TG2_P$18") (pintype "bidirectional"))
    )
    (net (code "52") (name "Net-(R32-Pad2)") (class "Default")
      (node (ref "R32") (pin "2") (pinfunction "2_2") (pintype "passive"))
      (node (ref "R9") (pin "1") (pinfunction "1_1") (pintype "passive"))
    )
    (net (code "53") (name "Net-(U$2-BST1)") (class "Default")
      (node (ref "C3") (pin "2") (pinfunction "2_2") (pintype "passive"))
      (node (ref "U$2") (pin "P$2") (pinfunction "BST1_P$2") (pintype "bidirectional"))
    )
    (net (code "54") (name "Net-(U$2-BST2)") (class "Default")
      (node (ref "C10") (pin "2") (pinfunction "2_2") (pintype "passive"))
      (node (ref "U$2") (pin "P$16") (pinfunction "BST2_P$16") (pintype "bidirectional"))
    )
    (net (code "55") (name "Net-(U$2-CTRL)") (class "Default")
      (node (ref "C5") (pin "1") (pinfunction "1_1") (pintype "passive"))
      (node (ref "U$2") (pin "P$11") (pinfunction "LOADEN_P$11") (pintype "bidirectional"))
      (node (ref "U$2") (pin "P$12") (pinfunction "VREF_P$12") (pintype "bidirectional"))
      (node (ref "U$2") (pin "P$13") (pinfunction "CTRL_P$13") (pintype "bidirectional"))
    )
    (net (code "56") (name "Net-(U$2-EN)") (class "Default")
      (node (ref "R2") (pin "1") (pinfunction "1_1") (pintype "passive"))
      (node (ref "R3") (pin "2") (pinfunction "2_2") (pintype "passive"))
      (node (ref "U$2") (pin "P$9") (pinfunction "EN_P$9") (pintype "bidirectional"))
    )
    (net (code "57") (name "Net-(U$2-FB)") (class "Default")
      (node (ref "R10") (pin "2") (pinfunction "2_2") (pintype "passive"))
      (node (ref "R32") (pin "1") (pinfunction "1_1") (pintype "passive"))
      (node (ref "U$2") (pin "P$24") (pinfunction "FB_P$24") (pintype "bidirectional"))
    )
    (net (code "58") (name "Net-(U$2-INTVCC)") (class "Default")
      (node (ref "C8") (pin "1") (pinfunction "1_1") (pintype "passive"))
      (node (ref "R6") (pin "2") (pinfunction "2_2") (pintype "passive"))
      (node (ref "U$2") (pin "P$8") (pinfunction "INTVCC_P$8") (pintype "bidirectional"))
    )
    (net (code "59") (name "Net-(U$2-LSN)") (class "Default")
      (node (ref "L1") (pin "P$1") (pinfunction "P$1_P$1") (pintype "bidirectional"))
      (node (ref "R7") (pin "1") (pinfunction "1_1") (pintype "passive"))
      (node (ref "U$2") (pin "P$6") (pinfunction "LSN_P$6") (pintype "bidirectional"))
    )
    (net (code "60") (name "Net-(U$2-LSP)") (class "Default")
      (node (ref "C3") (pin "1") (pinfunction "1_1") (pintype "passive"))
      (node (ref "M1") (pin "P$2") (pinfunction "S_P$2") (pintype "input"))
      (node (ref "M1") (pin "P$3") (pinfunction "S_P$3") (pintype "input"))
      (node (ref "M1") (pin "P$4") (pinfunction "S_P$4") (pintype "input"))
      (node (ref "M2") (pin "P$5") (pinfunction "D_P$5") (pintype "output"))
      (node (ref "M2") (pin "P$6") (pinfunction "D_P$6") (pintype "output"))
      (node (ref "M2") (pin "P$7") (pinfunction "D_P$7") (pintype "output"))
      (node (ref "M2") (pin "P$8") (pinfunction "D_P$8") (pintype "output"))
      (node (ref "M2") (pin "P$9") (pinfunction "D_P$9") (pintype "output"))
      (node (ref "R7") (pin "2") (pinfunction "2_2") (pintype "passive"))
      (node (ref "U$2") (pin "P$3") (pinfunction "SW1_P$3") (pintype "bidirectional"))
      (node (ref "U$2") (pin "P$5") (pinfunction "LSP_P$5") (pintype "bidirectional"))
    )
    (net (code "61") (name "Net-(U$2-NPGOOD)") (class "Default")
      (node (ref "R6") (pin "1") (pinfunction "1_1") (pintype "passive"))
      (node (ref "U$2") (pin "P$26") (pinfunction "NPGOOD_P$26") (pintype "bidirectional"))
    )
    (net (code "62") (name "Net-(U$2-RT)") (class "Default")
      (node (ref "R5") (pin "2") (pinfunction "2_2") (pintype "passive"))
      (node (ref "U$2") (pin "P$22") (pinfunction "RT_P$22") (pintype "bidirectional"))
    )
    (net (code "63") (name "Net-(U$2-SS)") (class "Default")
      (node (ref "C6") (pin "1") (pinfunction "1_1") (pintype "passive"))
      (node (ref "U$2") (pin "P$25") (pinfunction "SS_P$25") (pintype "bidirectional"))
    )
    (net (code "64") (name "Net-(U$2-SW2)") (class "Default")
      (node (ref "C10") (pin "1") (pinfunction "1_1") (pintype "passive"))
      (node (ref "L1") (pin "P$2") (pinfunction "P$2_P$2") (pintype "bidirectional"))
      (node (ref "M3") (pin "P$5") (pinfunction "D_P$5") (pintype "output"))
      (node (ref "M3") (pin "P$6") (pinfunction "D_P$6") (pintype "output"))
      (node (ref "M3") (pin "P$7") (pinfunction "D_P$7") (pintype "output"))
      (node (ref "M3") (pin "P$8") (pinfunction "D_P$8") (pintype "output"))
      (node (ref "M3") (pin "P$9") (pinfunction "D_P$9") (pintype "output"))
      (node (ref "M4") (pin "P$2") (pinfunction "S_P$2") (pintype "input"))
      (node (ref "M4") (pin "P$3") (pinfunction "S_P$3") (pintype "input"))
      (node (ref "M4") (pin "P$4") (pinfunction "S_P$4") (pintype "input"))
      (node (ref "U$2") (pin "P$17") (pinfunction "SW2_P$17") (pintype "bidirectional"))
    )
    (net (code "65") (name "Net-(U$2-VC)") (class "Default")
      (node (ref "C7") (pin "1") (pinfunction "1_1") (pintype "passive"))
      (node (ref "R4") (pin "2") (pinfunction "2_2") (pintype "passive"))
      (node (ref "U$2") (pin "P$23") (pinfunction "VC_P$23") (pintype "bidirectional"))
    )
    (net (code "66") (name "Net-(U1-ISEN12)") (class "Default")
      (node (ref "R11") (pin "2") (pinfunction "2_2") (pintype "passive"))
      (node (ref "U1") (pin "3") (pinfunction "ISEN12_3") (pintype "bidirectional"))
    )
    (net (code "67") (name "Net-(U1-ISEN34)") (class "Default")
      (node (ref "R12") (pin "2") (pinfunction "2_2") (pintype "passive"))
      (node (ref "U1") (pin "6") (pinfunction "ISEN34_6") (pintype "bidirectional"))
    )
    (net (code "68") (name "Net-(U2-ISEN12)") (class "Default")
      (node (ref "R14") (pin "2") (pinfunction "2_2") (pintype "passive"))
      (node (ref "U2") (pin "3") (pinfunction "ISEN12_3") (pintype "bidirectional"))
    )
    (net (code "69") (name "Net-(U2-ISEN34)") (class "Default")
      (node (ref "R15") (pin "2") (pinfunction "2_2") (pintype "passive"))
      (node (ref "U2") (pin "6") (pinfunction "ISEN34_6") (pintype "bidirectional"))
    )
    (net (code "70") (name "Net-(U5-BST)") (class "Default")
      (node (ref "C62") (pin "1") (pinfunction "1_1") (pintype "passive"))
      (node (ref "U5") (pin "1") (pinfunction "BST_1") (pintype "bidirectional"))
    )
    (net (code "71") (name "Net-(U5-FB)") (class "Default")
      (node (ref "C54") (pin "1") (pinfunction "1_1") (pintype "passive"))
      (node (ref "R53") (pin "1") (pinfunction "1_1") (pintype "passive"))
      (node (ref "R54") (pin "2") (pinfunction "2_2") (pintype "passive"))
      (node (ref "U5") (pin "6") (pinfunction "FB_6") (pintype "bidirectional"))
    )
    (net (code "72") (name "Net-(U5-INTVCC)") (class "Default")
      (node (ref "C53") (pin "1") (pinfunction "1_1") (pintype "passive"))
      (node (ref "U5") (pin "3") (pinfunction "INTVCC_3") (pintype "bidirectional"))
    )
    (net (code "73") (name "Net-(U5-PG)") (class "Default")
      (node (ref "R52") (pin "1") (pinfunction "1_1") (pintype "passive"))
      (node (ref "U5") (pin "8") (pinfunction "PG_8") (pintype "bidirectional"))
    )
    (net (code "74") (name "Net-(U5-RT)") (class "Default")
      (node (ref "R51") (pin "2") (pinfunction "2_2") (pintype "passive"))
      (node (ref "U5") (pin "4") (pinfunction "RT_4") (pintype "bidirectional"))
    )
    (net (code "75") (name "Net-(U5-SW)") (class "Default")
      (node (ref "C62") (pin "2") (pinfunction "2_2") (pintype "passive"))
      (node (ref "L6") (pin "1") (pinfunction "1_1") (pintype "bidirectional"))
      (node (ref "U5") (pin "2") (pinfunction "SW_2") (pintype "bidirectional"))
    )
    (net (code "76") (name "Net-(U5-TRSS)") (class "Default")
      (node (ref "C52") (pin "1") (pinfunction "1_1") (pintype "passive"))
      (node (ref "U5") (pin "7") (pinfunction "TRSS_7") (pintype "bidirectional"))
    )
    (net (code "77") (name "Net-(U11-CT)") (class "Default")
      (node (ref "R37") (pin "1") (pinfunction "1_1") (pintype "passive"))
      (node (ref "U11") (pin "6") (pinfunction "CT_6") (pintype "bidirectional"))
    )
    (net (code "78") (name "Net-(U11-INT)") (class "Default")
      (node (ref "R38") (pin "1") (pinfunction "1_1") (pintype "passive"))
      (node (ref "U11") (pin "5") (pinfunction "INT_5") (pintype "bidirectional"))
    )
    (net (code "79") (name "RPI_GND") (class "Default")
      (node (ref "J1") (pin "5") (pinfunction "5_5") (pintype "passive"))
      (node (ref "J2") (pin "5") (pinfunction "5_5") (pintype "passive"))
    )
    (net (code "80") (name "SCL1_I2C") (class "Default")
      (node (ref "J5") (pin "2") (pinfunction "2_2") (pintype "bidirectional"))
      (node (ref "X1") (pin "5") (pinfunction "P$5_5") (pintype "bidirectional"))
    )
    (net (code "81") (name "SDA1_I2C") (class "Default")
      (node (ref "J5") (pin "1") (pinfunction "1_1") (pintype "bidirectional"))
      (node (ref "X1") (pin "3") (pinfunction "P$3_3") (pintype "bidirectional"))
    )
    (net (code "82") (name "SPI0_CE0_N") (class "Default")
      (node (ref "J7") (pin "3") (pinfunction "3_3") (pintype "passive"))
      (node (ref "X1") (pin "24") (pinfunction "P$24_24") (pintype "bidirectional"))
    )
    (net (code "83") (name "SPI0_CE1_N") (class "Default")
      (node (ref "J7") (pin "5") (pinfunction "5_5") (pintype "passive"))
      (node (ref "X1") (pin "26") (pinfunction "P$26_26") (pintype "bidirectional"))
    )
    (net (code "84") (name "SPI0_CS") (class "Default")
      (node (ref "H1") (pin "1.10") (pinfunction "1.10_1.10") (pintype "bidirectional"))
      (node (ref "U11") (pin "4") (pinfunction "CS_4") (pintype "bidirectional"))
    )
    (net (code "85") (name "SPI0_MISO") (class "Default")
      (node (ref "J7") (pin "2") (pinfunction "2_2") (pintype "passive"))
      (node (ref "X1") (pin "21") (pinfunction "P$21_21") (pintype "bidirectional"))
    )
    (net (code "86") (name "SPI0_MOSI") (class "Default")
      (node (ref "J7") (pin "1") (pinfunction "1_1") (pintype "passive"))
      (node (ref "X1") (pin "19") (pinfunction "P$19_19") (pintype "bidirectional"))
    )
    (net (code "87") (name "SPI0_SCLK") (class "Default")
      (node (ref "J7") (pin "4") (pinfunction "4_4") (pintype "passive"))
      (node (ref "X1") (pin "23") (pinfunction "P$23_23") (pintype "bidirectional"))
    )
    (net (code "88") (name "SPI1_D0") (class "Default")
      (node (ref "H1") (pin "1.11") (pinfunction "1.11_1.11") (pintype "bidirectional"))
      (node (ref "U11") (pin "2") (pinfunction "DOUT_2") (pintype "bidirectional"))
    )
    (net (code "89") (name "SPI1_D1") (class "Default")
      (node (ref "H1") (pin "1.12") (pinfunction "1.12_1.12") (pintype "bidirectional"))
      (node (ref "U11") (pin "3") (pinfunction "DIN_3") (pintype "bidirectional"))
    )
    (net (code "90") (name "SPI1_SCLK") (class "Default")
      (node (ref "H1") (pin "1.9") (pinfunction "1.9_1.9") (pintype "bidirectional"))
      (node (ref "U11") (pin "1") (pinfunction "SCLK_1") (pintype "bidirectional"))
    )
    (net (code "91") (name "TORQUE_1A") (class "Default")
      (node (ref "J8") (pin "1") (pinfunction "1_1") (pintype "passive"))
      (node (ref "U1") (pin "2") (pinfunction "OUT1_2") (pintype "output"))
    )
    (net (code "92") (name "TORQUE_1B") (class "Default")
      (node (ref "J8") (pin "2") (pinfunction "2_2") (pintype "passive"))
      (node (ref "U1") (pin "4") (pinfunction "OUT2_4") (pintype "output"))
    )
    (net (code "93") (name "TORQUE_2A") (class "Default")
      (node (ref "J8") (pin "4") (pinfunction "4_4") (pintype "passive"))
      (node (ref "U1") (pin "7") (pinfunction "OUT3_7") (pintype "output"))
    )
    (net (code "94") (name "TORQUE_2B") (class "Default")
      (node (ref "J8") (pin "3") (pinfunction "3_3") (pintype "passive"))
      (node (ref "U1") (pin "5") (pinfunction "OUT4_5") (pintype "output"))
    )
    (net (code "95") (name "TORQUE_3A") (class "Default")
      (node (ref "J9") (pin "1") (pinfunction "1_1") (pintype "passive"))
      (node (ref "U2") (pin "2") (pinfunction "OUT1_2") (pintype "output"))
    )
    (net (code "96") (name "TORQUE_3B") (class "Default")
      (node (ref "J9") (pin "2") (pinfunction "2_2") (pintype "passive"))
      (node (ref "U2") (pin "4") (pinfunction "OUT2_4") (pintype "output"))
    )
    (net (code "97") (name "TORQUE_4A") (class "Default")
      (node (ref "J9") (pin "4") (pinfunction "4_4") (pintype "passive"))
      (node (ref "U2") (pin "7") (pinfunction "OUT3_7") (pintype "output"))
    )
    (net (code "98") (name "TORQUE_4B") (class "Default")
      (node (ref "J9") (pin "3") (pinfunction "3_3") (pintype "passive"))
      (node (ref "U2") (pin "5") (pinfunction "OUT4_5") (pintype "output"))
    )
    (net (code "99") (name "VCC") (class "Default")
      (node (ref "C13") (pin "1") (pinfunction "1_1") (pintype "passive"))
      (node (ref "C78") (pin "1") (pinfunction "1_1") (pintype "passive"))
      (node (ref "C79") (pin "1") (pinfunction "1_1") (pintype "passive"))
      (node (ref "C80") (pin "1") (pinfunction "1_1") (pintype "passive"))
      (node (ref "C81") (pin "1") (pinfunction "1_1") (pintype "passive"))
      (node (ref "D4") (pin "A") (pinfunction "A_A") (pintype "passive"))
      (node (ref "D4") (pin "C") (pinfunction "C_C") (pintype "passive"))
      (node (ref "R46") (pin "1") (pinfunction "1_1") (pintype "passive"))
      (node (ref "R8") (pin "2") (pinfunction "2_2") (pintype "passive"))
      (node (ref "R9") (pin "2") (pinfunction "2_2") (pintype "passive"))
      (node (ref "U$2") (pin "P$28") (pinfunction "ISN_P$28") (pintype "bidirectional"))
      (node (ref "U5") (pin "9") (pinfunction "VIN_9") (pintype "bidirectional"))
    )
    (net (code "100") (name "V_BATT") (class "Default")
      (node (ref "C1") (pin "1") (pinfunction "1_1") (pintype "passive"))
      (node (ref "C15") (pin "1") (pinfunction "1_1") (pintype "passive"))
      (node (ref "C16") (pin "1") (pinfunction "1_1") (pintype "passive"))
      (node (ref "C2") (pin "1") (pinfunction "1_1") (pintype "passive"))
      (node (ref "C4") (pin "1") (pinfunction "1_1") (pintype "passive"))
      (node (ref "H1") (pin "2.45") (pinfunction "2.45_2.45") (pintype "bidirectional"))
      (node (ref "H1") (pin "2.46") (pinfunction "2.46_2.46") (pintype "bidirectional"))
      (node (ref "M1") (pin "P$5") (pinfunction "D_P$5") (pintype "output"))
      (node (ref "M1") (pin "P$6") (pinfunction "D_P$6") (pintype "output"))
      (node (ref "M1") (pin "P$7") (pinfunction "D_P$7") (pintype "output"))
      (node (ref "M1") (pin "P$8") (pinfunction "D_P$8") (pintype "output"))
      (node (ref "M1") (pin "P$9") (pinfunction "D_P$9") (pintype "output"))
      (node (ref "R2") (pin "2") (pinfunction "2_2") (pintype "passive"))
      (node (ref "U$2") (pin "P$7") (pinfunction "VIN_P$7") (pintype "bidirectional"))
    )
    (net (code "101") (name "V_BATT_SENSE") (class "Default")
      (node (ref "R46") (pin "2") (pinfunction "2_2") (pintype "passive"))
      (node (ref "R47") (pin "2") (pinfunction "2_2") (pintype "passive"))
    )
    (net (code "102") (name "unconnected-(C13-Pad2)") (class "Default")
      (node (ref "C13") (pin "2") (pinfunction "2_2") (pintype "passive"))
    )
    (net (code "103") (name "unconnected-(H1-Pad1.1)") (class "Default")
      (node (ref "H1") (pin "1.1") (pinfunction "1.1_1.1") (pintype "bidirectional"))
    )
    (net (code "104") (name "unconnected-(H1-Pad1.2)") (class "Default")
      (node (ref "H1") (pin "1.2") (pinfunction "1.2_1.2") (pintype "bidirectional"))
    )
    (net (code "105") (name "unconnected-(H1-Pad1.3)") (class "Default")
      (node (ref "H1") (pin "1.3") (pinfunction "1.3_1.3") (pintype "bidirectional"))
    )
    (net (code "106") (name "unconnected-(H1-Pad1.4)") (class "Default")
      (node (ref "H1") (pin "1.4") (pinfunction "1.4_1.4") (pintype "bidirectional"))
    )
    (net (code "107") (name "unconnected-(H1-Pad1.5)") (class "Default")
      (node (ref "H1") (pin "1.5") (pinfunction "1.5_1.5") (pintype "bidirectional"))
    )
    (net (code "108") (name "unconnected-(H1-Pad1.6)") (class "Default")
      (node (ref "H1") (pin "1.6") (pinfunction "1.6_1.6") (pintype "bidirectional"))
    )
    (net (code "109") (name "unconnected-(H1-Pad1.7)") (class "Default")
      (node (ref "H1") (pin "1.7") (pinfunction "1.7_1.7") (pintype "bidirectional"))
    )
    (net (code "110") (name "unconnected-(H1-Pad1.8)") (class "Default")
      (node (ref "H1") (pin "1.8") (pinfunction "1.8_1.8") (pintype "bidirectional"))
    )
    (net (code "111") (name "unconnected-(H1-Pad1.13)") (class "Default")
      (node (ref "H1") (pin "1.13") (pinfunction "1.13_1.13") (pintype "bidirectional"))
    )
    (net (code "112") (name "unconnected-(H1-Pad1.14)") (class "Default")
      (node (ref "H1") (pin "1.14") (pinfunction "1.14_1.14") (pintype "bidirectional"))
    )
    (net (code "113") (name "unconnected-(H1-Pad1.15)") (class "Default")
      (node (ref "H1") (pin "1.15") (pinfunction "1.15_1.15") (pintype "bidirectional"))
    )
    (net (code "114") (name "unconnected-(H1-Pad1.16)") (class "Default")
      (node (ref "H1") (pin "1.16") (pinfunction "1.16_1.16") (pintype "bidirectional"))
    )
    (net (code "115") (name "unconnected-(H1-Pad1.21)") (class "Default")
      (node (ref "H1") (pin "1.21") (pinfunction "1.21_1.21") (pintype "bidirectional"))
    )
    (net (code "116") (name "unconnected-(H1-Pad1.22)") (class "Default")
      (node (ref "H1") (pin "1.22") (pinfunction "1.22_1.22") (pintype "bidirectional"))
    )
    (net (code "117") (name "unconnected-(H1-Pad1.31)") (class "Default")
      (node (ref "H1") (pin "1.31") (pinfunction "1.31_1.31") (pintype "bidirectional"))
    )
    (net (code "118") (name "unconnected-(H1-Pad1.32)") (class "Default")
      (node (ref "H1") (pin "1.32") (pinfunction "1.32_1.32") (pintype "bidirectional"))
    )
    (net (code "119") (name "unconnected-(H1-Pad1.33)") (class "Default")
      (node (ref "H1") (pin "1.33") (pinfunction "1.33_1.33") (pintype "bidirectional"))
    )
    (net (code "120") (name "unconnected-(H1-Pad1.34)") (class "Default")
      (node (ref "H1") (pin "1.34") (pinfunction "1.34_1.34") (pintype "bidirectional"))
    )
    (net (code "121") (name "unconnected-(H1-Pad1.35)") (class "Default")
      (node (ref "H1") (pin "1.35") (pinfunction "1.35_1.35") (pintype "bidirectional"))
    )
    (net (code "122") (name "unconnected-(H1-Pad1.36)") (class "Default")
      (node (ref "H1") (pin "1.36") (pinfunction "1.36_1.36") (pintype "bidirectional"))
    )
    (net (code "123") (name "unconnected-(H1-Pad1.37)") (class "Default")
      (node (ref "H1") (pin "1.37") (pinfunction "1.37_1.37") (pintype "bidirectional"))
    )
    (net (code "124") (name "unconnected-(H1-Pad1.39)") (class "Default")
      (node (ref "H1") (pin "1.39") (pinfunction "1.39_1.39") (pintype "bidirectional"))
    )
    (net (code "125") (name "unconnected-(H1-Pad1.41)") (class "Default")
      (node (ref "H1") (pin "1.41") (pinfunction "1.41_1.41") (pintype "bidirectional"))
    )
    (net (code "126") (name "unconnected-(H1-Pad1.43)") (class "Default")
      (node (ref "H1") (pin "1.43") (pinfunction "1.43_1.43") (pintype "bidirectional"))
    )
    (net (code "127") (name "unconnected-(H1-Pad1.45)") (class "Default")
      (node (ref "H1") (pin "1.45") (pinfunction "1.45_1.45") (pintype "bidirectional"))
    )
    (net (code "128") (name "unconnected-(H1-Pad1.47)") (class "Default")
      (node (ref "H1") (pin "1.47") (pinfunction "1.47_1.47") (pintype "bidirectional"))
    )
    (net (code "129") (name "unconnected-(H1-Pad1.49)") (class "Default")
      (node (ref "H1") (pin "1.49") (pinfunction "1.49_1.49") (pintype "bidirectional"))
    )
    (net (code "130") (name "unconnected-(H1-Pad1.50)") (class "Default")
      (node (ref "H1") (pin "1.50") (pinfunction "1.50_1.50") (pintype "bidirectional"))
    )
    (net (code "131") (name "unconnected-(H1-Pad1.51)") (class "Default")
      (node (ref "H1") (pin "1.51") (pinfunction "1.51_1.51") (pintype "bidirectional"))
    )
    (net (code "132") (name "unconnected-(H1-Pad1.52)") (class "Default")
      (node (ref "H1") (pin "1.52") (pinfunction "1.52_1.52") (pintype "bidirectional"))
    )
    (net (code "133") (name "unconnected-(H1-Pad2.1)") (class "Default")
      (node (ref "H1") (pin "2.1") (pinfunction "2.1_2.1") (pintype "bidirectional"))
    )
    (net (code "134") (name "unconnected-(H1-Pad2.2)") (class "Default")
      (node (ref "H1") (pin "2.2") (pinfunction "2.2_2.2") (pintype "bidirectional"))
    )
    (net (code "135") (name "unconnected-(H1-Pad2.3)") (class "Default")
      (node (ref "H1") (pin "2.3") (pinfunction "2.3_2.3") (pintype "bidirectional"))
    )
    (net (code "136") (name "unconnected-(H1-Pad2.4)") (class "Default")
      (node (ref "H1") (pin "2.4") (pinfunction "2.4_2.4") (pintype "bidirectional"))
    )
    (net (code "137") (name "unconnected-(H1-Pad2.5)") (class "Default")
      (node (ref "H1") (pin "2.5") (pinfunction "2.5_2.5") (pintype "bidirectional"))
    )
    (net (code "138") (name "unconnected-(H1-Pad2.6)") (class "Default")
      (node (ref "H1") (pin "2.6") (pinfunction "2.6_2.6") (pintype "bidirectional"))
    )
    (net (code "139") (name "unconnected-(H1-Pad2.9)") (class "Default")
      (node (ref "H1") (pin "2.9") (pinfunction "2.9_2.9") (pintype "bidirectional"))
    )
    (net (code "140") (name "unconnected-(H1-Pad2.10)") (class "Default")
      (node (ref "H1") (pin "2.10") (pinfunction "2.10_2.10") (pintype "bidirectional"))
    )
    (net (code "141") (name "unconnected-(H1-Pad2.11)") (class "Default")
      (node (ref "H1") (pin "2.11") (pinfunction "2.11_2.11") (pintype "bidirectional"))
    )
    (net (code "142") (name "unconnected-(H1-Pad2.12)") (class "Default")
      (node (ref "H1") (pin "2.12") (pinfunction "2.12_2.12") (pintype "bidirectional"))
    )
    (net (code "143") (name "unconnected-(H1-Pad2.18)") (class "Default")
      (node (ref "H1") (pin "2.18") (pinfunction "2.18_2.18") (pintype "bidirectional"))
    )
    (net (code "144") (name "unconnected-(H1-Pad2.23)") (class "Default")
      (node (ref "H1") (pin "2.23") (pinfunction "2.23_2.23") (pintype "bidirectional"))
    )
    (net (code "145") (name "unconnected-(H1-Pad2.24)") (class "Default")
      (node (ref "H1") (pin "2.24") (pinfunction "2.24_2.24") (pintype "bidirectional"))
    )
    (net (code "146") (name "unconnected-(H1-Pad2.31)") (class "Default")
      (node (ref "H1") (pin "2.31") (pinfunction "2.31_2.31") (pintype "bidirectional"))
    )
    (net (code "147") (name "unconnected-(H1-Pad2.33)") (class "Default")
      (node (ref "H1") (pin "2.33") (pinfunction "2.33_2.33") (pintype "bidirectional"))
    )
    (net (code "148") (name "unconnected-(H1-Pad2.34)") (class "Default")
      (node (ref "H1") (pin "2.34") (pinfunction "2.34_2.34") (pintype "bidirectional"))
    )
    (net (code "149") (name "unconnected-(H1-Pad2.35)") (class "Default")
      (node (ref "H1") (pin "2.35") (pinfunction "2.35_2.35") (pintype "bidirectional"))
    )
    (net (code "150") (name "unconnected-(H1-Pad2.36)") (class "Default")
      (node (ref "H1") (pin "2.36") (pinfunction "2.36_2.36") (pintype "bidirectional"))
    )
    (net (code "151") (name "unconnected-(H1-Pad2.37)") (class "Default")
      (node (ref "H1") (pin "2.37") (pinfunction "2.37_2.37") (pintype "bidirectional"))
    )
    (net (code "152") (name "unconnected-(H1-Pad2.38)") (class "Default")
      (node (ref "H1") (pin "2.38") (pinfunction "2.38_2.38") (pintype "bidirectional"))
    )
    (net (code "153") (name "unconnected-(H1-Pad2.39)") (class "Default")
      (node (ref "H1") (pin "2.39") (pinfunction "2.39_2.39") (pintype "bidirectional"))
    )
    (net (code "154") (name "unconnected-(H1-Pad2.40)") (class "Default")
      (node (ref "H1") (pin "2.40") (pinfunction "2.40_2.40") (pintype "bidirectional"))
    )
    (net (code "155") (name "unconnected-(H1-Pad2.41)") (class "Default")
      (node (ref "H1") (pin "2.41") (pinfunction "2.41_2.41") (pintype "bidirectional"))
    )
    (net (code "156") (name "unconnected-(H1-Pad2.42)") (class "Default")
      (node (ref "H1") (pin "2.42") (pinfunction "2.42_2.42") (pintype "bidirectional"))
    )
    (net (code "157") (name "unconnected-(H1-Pad2.43)") (class "Default")
      (node (ref "H1") (pin "2.43") (pinfunction "2.43_2.43") (pintype "bidirectional"))
    )
    (net (code "158") (name "unconnected-(H1-Pad2.44)") (class "Default")
      (node (ref "H1") (pin "2.44") (pinfunction "2.44_2.44") (pintype "bidirectional"))
    )
    (net (code "159") (name "unconnected-(H1-Pad2.49)") (class "Default")
      (node (ref "H1") (pin "2.49") (pinfunction "2.49_2.49") (pintype "bidirectional"))
    )
    (net (code "160") (name "unconnected-(H1-Pad2.50)") (class "Default")
      (node (ref "H1") (pin "2.50") (pinfunction "2.50_2.50") (pintype "bidirectional"))
    )
    (net (code "161") (name "unconnected-(H1-Pad2.51)") (class "Default")
      (node (ref "H1") (pin "2.51") (pinfunction "2.51_2.51") (pintype "bidirectional"))
    )
    (net (code "162") (name "unconnected-(H1-Pad2.52)") (class "Default")
      (node (ref "H1") (pin "2.52") (pinfunction "2.52_2.52") (pintype "bidirectional"))
    )
    (net (code "163") (name "unconnected-(H1-PadP$1)") (class "Default")
      (node (ref "H1") (pin "P$1") (pinfunction "P$1_P$1") (pintype "bidirectional"))
    )
    (net (code "164") (name "unconnected-(H1-PadP$2)") (class "Default")
      (node (ref "H1") (pin "P$2") (pinfunction "P$2_P$2") (pintype "bidirectional"))
    )
    (net (code "165") (name "unconnected-(H1-PadP$3)") (class "Default")
      (node (ref "H1") (pin "P$3") (pinfunction "P$3_P$3") (pintype "bidirectional"))
    )
    (net (code "166") (name "unconnected-(J8-MNT_1-Pad5)") (class "Default")
      (node (ref "J8") (pin "5") (pinfunction "MNT_1_5") (pintype "passive"))
    )
    (net (code "167") (name "unconnected-(J8-MNT_2-Pad6)") (class "Default")
      (node (ref "J8") (pin "6") (pinfunction "MNT_2_6") (pintype "passive"))
    )
    (net (code "168") (name "unconnected-(J9-MNT_1-Pad5)") (class "Default")
      (node (ref "J9") (pin "5") (pinfunction "MNT_1_5") (pintype "passive"))
    )
    (net (code "169") (name "unconnected-(J9-MNT_2-Pad6)") (class "Default")
      (node (ref "J9") (pin "6") (pinfunction "MNT_2_6") (pintype "passive"))
    )
    (net (code "170") (name "unconnected-(U$2-ISMON-PadP$27)") (class "Default")
      (node (ref "U$2") (pin "P$27") (pinfunction "ISMON_P$27") (pintype "bidirectional"))
    )
    (net (code "171") (name "unconnected-(U$2-LOADTG-PadP$20)") (class "Default")
      (node (ref "U$2") (pin "P$20") (pinfunction "LOADTG_P$20") (pintype "bidirectional"))
    )
    (net (code "172") (name "unconnected-(U1-MODE-Pad14)") (class "Default")
      (node (ref "U1") (pin "14") (pinfunction "MODE_14") (pintype "bidirectional"))
    )
    (net (code "173") (name "unconnected-(U2-MODE-Pad14)") (class "Default")
      (node (ref "U2") (pin "14") (pinfunction "MODE_14") (pintype "bidirectional"))
    )
    (net (code "174") (name "unconnected-(X1-P$2-Pad2)") (class "Default")
      (node (ref "X1") (pin "2") (pinfunction "P$2_2") (pintype "bidirectional"))
    )
    (net (code "175") (name "unconnected-(X1-P$4-Pad4)") (class "Default")
      (node (ref "X1") (pin "4") (pinfunction "P$4_4") (pintype "bidirectional"))
    )
    (net (code "176") (name "unconnected-(X1-P$6-Pad6)") (class "Default")
      (node (ref "X1") (pin "6") (pinfunction "P$6_6") (pintype "bidirectional"))
    )
    (net (code "177") (name "unconnected-(X1-P$7-Pad7)") (class "Default")
      (node (ref "X1") (pin "7") (pinfunction "P$7_7") (pintype "bidirectional"))
    )
    (net (code "178") (name "unconnected-(X1-P$8-Pad8)") (class "Default")
      (node (ref "X1") (pin "8") (pinfunction "P$8_8") (pintype "bidirectional"))
    )
    (net (code "179") (name "unconnected-(X1-P$9-Pad9)") (class "Default")
      (node (ref "X1") (pin "9") (pinfunction "P$9_9") (pintype "bidirectional"))
    )
    (net (code "180") (name "unconnected-(X1-P$10-Pad10)") (class "Default")
      (node (ref "X1") (pin "10") (pinfunction "P$10_10") (pintype "bidirectional"))
    )
    (net (code "181") (name "unconnected-(X1-P$12-Pad12)") (class "Default")
      (node (ref "X1") (pin "12") (pinfunction "P$12_12") (pintype "bidirectional"))
    )
    (net (code "182") (name "unconnected-(X1-P$14-Pad14)") (class "Default")
      (node (ref "X1") (pin "14") (pinfunction "P$14_14") (pintype "bidirectional"))
    )
    (net (code "183") (name "unconnected-(X1-P$17-Pad17)") (class "Default")
      (node (ref "X1") (pin "17") (pinfunction "P$17_17") (pintype "bidirectional"))
    )
    (net (code "184") (name "unconnected-(X1-P$20-Pad20)") (class "Default")
      (node (ref "X1") (pin "20") (pinfunction "P$20_20") (pintype "bidirectional"))
    )
    (net (code "185") (name "unconnected-(X1-P$25-Pad25)") (class "Default")
      (node (ref "X1") (pin "25") (pinfunction "P$25_25") (pintype "bidirectional"))
    )
    (net (code "186") (name "unconnected-(X1-P$27-Pad27)") (class "Default")
      (node (ref "X1") (pin "27") (pinfunction "P$27_27") (pintype "bidirectional"))
    )
    (net (code "187") (name "unconnected-(X1-P$28-Pad28)") (class "Default")
      (node (ref "X1") (pin "28") (pinfunction "P$28_28") (pintype "bidirectional"))
    )
    (net (code "188") (name "unconnected-(X1-P$29-Pad29)") (class "Default")
      (node (ref "X1") (pin "29") (pinfunction "P$29_29") (pintype "bidirectional"))
    )
    (net (code "189") (name "unconnected-(X1-P$30-Pad30)") (class "Default")
      (node (ref "X1") (pin "30") (pinfunction "P$30_30") (pintype "bidirectional"))
    )
    (net (code "190") (name "unconnected-(X1-P$34-Pad34)") (class "Default")
      (node (ref "X1") (pin "34") (pinfunction "P$34_34") (pintype "bidirectional"))
    )
    (net (code "191") (name "unconnected-(X1-P$39-Pad39)") (class "Default")
      (node (ref "X1") (pin "39") (pinfunction "P$39_39") (pintype "bidirectional"))
    )
    (net (code "192") (name "unconnected-(X2-Pad1)") (class "Default")
      (node (ref "X2") (pin "1") (pinfunction "1_1") (pintype "passive"))
    )
    (net (code "193") (name "unconnected-(X2AA-1-Pad33)") (class "Default")
      (node (ref "X2") (pin "33") (pinfunction "1_33") (pintype "passive"))
    )
    (net (code "194") (name "unconnected-(X2AB-1-Pad34)") (class "Default")
      (node (ref "X2") (pin "34") (pinfunction "1_34") (pintype "passive"))
    )
    (net (code "195") (name "unconnected-(X2AC-1-Pad35)") (class "Default")
      (node (ref "X2") (pin "35") (pinfunction "1_35") (pintype "passive"))
    )
    (net (code "196") (name "unconnected-(X2AD-1-Pad36)") (class "Default")
      (node (ref "X2") (pin "36") (pinfunction "1_36") (pintype "passive"))
    )
    (net (code "197") (name "unconnected-(X2AE-1-Pad37)") (class "Default")
      (node (ref "X2") (pin "37") (pinfunction "1_37") (pintype "passive"))
    )
    (net (code "198") (name "unconnected-(X2AF-1-Pad38)") (class "Default")
      (node (ref "X2") (pin "38") (pinfunction "1_38") (pintype "passive"))
    )
    (net (code "199") (name "unconnected-(X2AG-1-Pad39)") (class "Default")
      (node (ref "X2") (pin "39") (pinfunction "1_39") (pintype "passive"))
    )
    (net (code "200") (name "unconnected-(X2AH-1-Pad4)") (class "Default")
      (node (ref "X2") (pin "4") (pinfunction "1_4") (pintype "passive"))
    )
    (net (code "201") (name "unconnected-(X2AI-1-Pad40)") (class "Default")
      (node (ref "X2") (pin "40") (pinfunction "1_40") (pintype "passive"))
    )
    (net (code "202") (name "unconnected-(X2AJ-1-Pad5)") (class "Default")
      (node (ref "X2") (pin "5") (pinfunction "1_5") (pintype "passive"))
    )
    (net (code "203") (name "unconnected-(X2AK-1-Pad6)") (class "Default")
      (node (ref "X2") (pin "6") (pinfunction "1_6") (pintype "passive"))
    )
    (net (code "204") (name "unconnected-(X2AL-1-Pad7)") (class "Default")
      (node (ref "X2") (pin "7") (pinfunction "1_7") (pintype "passive"))
    )
    (net (code "205") (name "unconnected-(X2AM-1-Pad8)") (class "Default")
      (node (ref "X2") (pin "8") (pinfunction "1_8") (pintype "passive"))
    )
    (net (code "206") (name "unconnected-(X2AN-1-Pad9)") (class "Default")
      (node (ref "X2") (pin "9") (pinfunction "1_9") (pintype "passive"))
    )
    (net (code "207") (name "unconnected-(X2B-1-Pad10)") (class "Default")
      (node (ref "X2") (pin "10") (pinfunction "1_10") (pintype "passive"))
    )
    (net (code "208") (name "unconnected-(X2C-1-Pad11)") (class "Default")
      (node (ref "X2") (pin "11") (pinfunction "1_11") (pintype "passive"))
    )
    (net (code "209") (name "unconnected-(X2D-1-Pad12)") (class "Default")
      (node (ref "X2") (pin "12") (pinfunction "1_12") (pintype "passive"))
    )
    (net (code "210") (name "unconnected-(X2E-1-Pad13)") (class "Default")
      (node (ref "X2") (pin "13") (pinfunction "1_13") (pintype "passive"))
    )
    (net (code "211") (name "unconnected-(X2F-1-Pad14)") (class "Default")
      (node (ref "X2") (pin "14") (pinfunction "1_14") (pintype "passive"))
    )
    (net (code "212") (name "unconnected-(X2G-1-Pad15)") (class "Default")
      (node (ref "X2") (pin "15") (pinfunction "1_15") (pintype "passive"))
    )
    (net (code "213") (name "unconnected-(X2H-1-Pad16)") (class "Default")
      (node (ref "X2") (pin "16") (pinfunction "1_16") (pintype "passive"))
    )
    (net (code "214") (name "unconnected-(X2I-1-Pad17)") (class "Default")
      (node (ref "X2") (pin "17") (pinfunction "1_17") (pintype "passive"))
    )
    (net (code "215") (name "unconnected-(X2J-1-Pad18)") (class "Default")
      (node (ref "X2") (pin "18") (pinfunction "1_18") (pintype "passive"))
    )
    (net (code "216") (name "unconnected-(X2K-1-Pad19)") (class "Default")
      (node (ref "X2") (pin "19") (pinfunction "1_19") (pintype "passive"))
    )
    (net (code "217") (name "unconnected-(X2L-1-Pad2)") (class "Default")
      (node (ref "X2") (pin "2") (pinfunction "1_2") (pintype "passive"))
    )
    (net (code "218") (name "unconnected-(X2M-1-Pad20)") (class "Default")
      (node (ref "X2") (pin "20") (pinfunction "1_20") (pintype "passive"))
    )
    (net (code "219") (name "unconnected-(X2N-1-Pad21)") (class "Default")
      (node (ref "X2") (pin "21") (pinfunction "1_21") (pintype "passive"))
    )
    (net (code "220") (name "unconnected-(X2O-1-Pad22)") (class "Default")
      (node (ref "X2") (pin "22") (pinfunction "1_22") (pintype "passive"))
    )
    (net (code "221") (name "unconnected-(X2P-1-Pad23)") (class "Default")
      (node (ref "X2") (pin "23") (pinfunction "1_23") (pintype "passive"))
    )
    (net (code "222") (name "unconnected-(X2Q-1-Pad24)") (class "Default")
      (node (ref "X2") (pin "24") (pinfunction "1_24") (pintype "passive"))
    )
    (net (code "223") (name "unconnected-(X2R-1-Pad25)") (class "Default")
      (node (ref "X2") (pin "25") (pinfunction "1_25") (pintype "passive"))
    )
    (net (code "224") (name "unconnected-(X2S-1-Pad26)") (class "Default")
      (node (ref "X2") (pin "26") (pinfunction "1_26") (pintype "passive"))
    )
    (net (code "225") (name "unconnected-(X2T-1-Pad27)") (class "Default")
      (node (ref "X2") (pin "27") (pinfunction "1_27") (pintype "passive"))
    )
    (net (code "226") (name "unconnected-(X2U-1-Pad28)") (class "Default")
      (node (ref "X2") (pin "28") (pinfunction "1_28") (pintype "passive"))
    )
    (net (code "227") (name "unconnected-(X2V-1-Pad29)") (class "Default")
      (node (ref "X2") (pin "29") (pinfunction "1_29") (pintype "passive"))
    )
    (net (code "228") (name "unconnected-(X2W-1-Pad3)") (class "Default")
      (node (ref "X2") (pin "3") (pinfunction "1_3") (pintype "passive"))
    )
    (net (code "229") (name "unconnected-(X2X-1-Pad30)") (class "Default")
      (node (ref "X2") (pin "30") (pinfunction "1_30") (pintype "passive"))
    )
    (net (code "230") (name "unconnected-(X2Y-1-Pad31)") (class "Default")
      (node (ref "X2") (pin "31") (pinfunction "1_31") (pintype "passive"))
    )
    (net (code "231") (name "unconnected-(X2Z-1-Pad32)") (class "Default")
      (node (ref "X2") (pin "32") (pinfunction "1_32") (pintype "passive"))
    )
  )
)
